# Callisto_LSOx10_v1p2.net
KiCad netlist of a schematic drawn in EAGLE
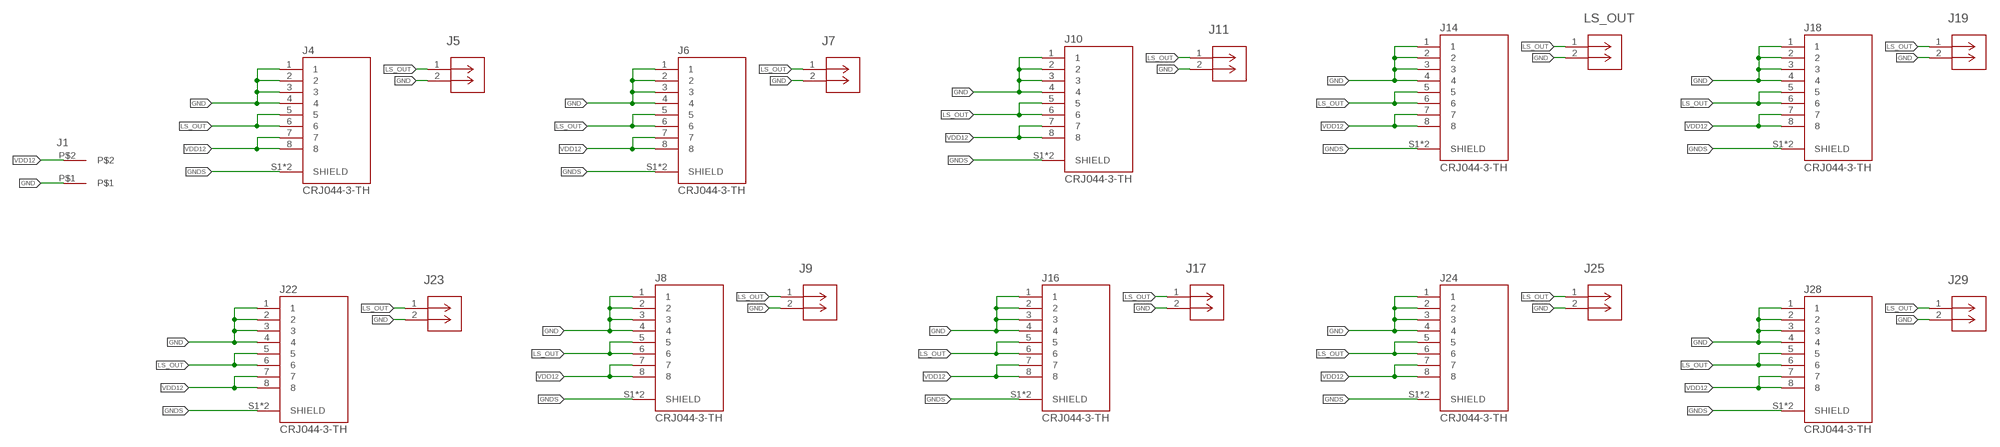
[diagram p0: schematic, sheet 1]

(export (version "E")
  (design (tool "Eeschema 10.0.6"))
  (components
    (comp (ref "J1")
      (value "2-pos")
      (footprint "eagle-import:2_3.81MM_PITCH")
      (fields (field (name "PARTNO") "691322310002"))
      (libsource (lib "eagle-import") (part "3.81MM_1_X_2_RT_ANGLE_PLUG_HEADER"))
    )
    (comp (ref "J4")
      (value "CRJ044-3-TH")
      (footprint "eagle-import:CUI_CRJ044-3-TH")
      (libsource (lib "eagle-import") (part "CRJ044-3-TH"))
    )
    (comp (ref "J5")
      (value "CONN_530470210_PICOBLADE_X_2")
      (footprint "eagle-import:CON_530470210_MOL")
      (fields
        (field (name "MANUFACTURER_PART_NUMBER") "530470210")
        (field (name "COPYRIGHT") "Copyright (C) 2022 Ultra Librarian. All rights reserved.")
      )
      (libsource (lib "eagle-import") (part "CONN_530470210_PICOBLADE_X_2"))
    )
    (comp (ref "J6")
      (value "CRJ044-3-TH")
      (footprint "eagle-import:CUI_CRJ044-3-TH")
      (libsource (lib "eagle-import") (part "CRJ044-3-TH"))
    )
    (comp (ref "J7")
      (value "CONN_530470210_PICOBLADE_X_2")
      (footprint "eagle-import:CON_530470210_MOL")
      (fields
        (field (name "MANUFACTURER_PART_NUMBER") "530470210")
        (field (name "COPYRIGHT") "Copyright (C) 2022 Ultra Librarian. All rights reserved.")
      )
      (libsource (lib "eagle-import") (part "CONN_530470210_PICOBLADE_X_2"))
    )
    (comp (ref "J8")
      (value "CRJ044-3-TH")
      (footprint "eagle-import:CUI_CRJ044-3-TH")
      (libsource (lib "eagle-import") (part "CRJ044-3-TH"))
    )
    (comp (ref "J9")
      (value "CONN_530470210_PICOBLADE_X_2")
      (footprint "eagle-import:CON_530470210_MOL")
      (fields
        (field (name "MANUFACTURER_PART_NUMBER") "530470210")
        (field (name "COPYRIGHT") "Copyright (C) 2022 Ultra Librarian. All rights reserved.")
      )
      (libsource (lib "eagle-import") (part "CONN_530470210_PICOBLADE_X_2"))
    )
    (comp (ref "J10")
      (value "CRJ044-3-TH")
      (footprint "eagle-import:CUI_CRJ044-3-TH")
      (libsource (lib "eagle-import") (part "CRJ044-3-TH"))
    )
    (comp (ref "J11")
      (value "CONN_530470210_PICOBLADE_X_2")
      (footprint "eagle-import:CON_530470210_MOL")
      (fields
        (field (name "MANUFACTURER_PART_NUMBER") "530470210")
        (field (name "COPYRIGHT") "Copyright (C) 2022 Ultra Librarian. All rights reserved.")
      )
      (libsource (lib "eagle-import") (part "CONN_530470210_PICOBLADE_X_2"))
    )
    (comp (ref "J14")
      (value "CRJ044-3-TH")
      (footprint "eagle-import:CUI_CRJ044-3-TH")
      (libsource (lib "eagle-import") (part "CRJ044-3-TH"))
    )
    (comp (ref "J16")
      (value "CRJ044-3-TH")
      (footprint "eagle-import:CUI_CRJ044-3-TH")
      (libsource (lib "eagle-import") (part "CRJ044-3-TH"))
    )
    (comp (ref "J17")
      (value "CONN_530470210_PICOBLADE_X_2")
      (footprint "eagle-import:CON_530470210_MOL")
      (fields
        (field (name "MANUFACTURER_PART_NUMBER") "530470210")
        (field (name "COPYRIGHT") "Copyright (C) 2022 Ultra Librarian. All rights reserved.")
      )
      (libsource (lib "eagle-import") (part "CONN_530470210_PICOBLADE_X_2"))
    )
    (comp (ref "J18")
      (value "CRJ044-3-TH")
      (footprint "eagle-import:CUI_CRJ044-3-TH")
      (libsource (lib "eagle-import") (part "CRJ044-3-TH"))
    )
    (comp (ref "J19")
      (value "CONN_530470210_PICOBLADE_X_2")
      (footprint "eagle-import:CON_530470210_MOL")
      (fields
        (field (name "MANUFACTURER_PART_NUMBER") "530470210")
        (field (name "COPYRIGHT") "Copyright (C) 2022 Ultra Librarian. All rights reserved.")
      )
      (libsource (lib "eagle-import") (part "CONN_530470210_PICOBLADE_X_2"))
    )
    (comp (ref "J22")
      (value "CRJ044-3-TH")
      (footprint "eagle-import:CUI_CRJ044-3-TH")
      (libsource (lib "eagle-import") (part "CRJ044-3-TH"))
    )
    (comp (ref "J23")
      (value "CONN_530470210_PICOBLADE_X_2")
      (footprint "eagle-import:CON_530470210_MOL")
      (fields
        (field (name "MANUFACTURER_PART_NUMBER") "530470210")
        (field (name "COPYRIGHT") "Copyright (C) 2022 Ultra Librarian. All rights reserved.")
      )
      (libsource (lib "eagle-import") (part "CONN_530470210_PICOBLADE_X_2"))
    )
    (comp (ref "J24")
      (value "CRJ044-3-TH")
      (footprint "eagle-import:CUI_CRJ044-3-TH")
      (libsource (lib "eagle-import") (part "CRJ044-3-TH"))
    )
    (comp (ref "J25")
      (value "CONN_530470210_PICOBLADE_X_2")
      (footprint "eagle-import:CON_530470210_MOL")
      (fields
        (field (name "MANUFACTURER_PART_NUMBER") "530470210")
        (field (name "COPYRIGHT") "Copyright (C) 2022 Ultra Librarian. All rights reserved.")
      )
      (libsource (lib "eagle-import") (part "CONN_530470210_PICOBLADE_X_2"))
    )
    (comp (ref "J28")
      (value "CRJ044-3-TH")
      (footprint "eagle-import:CUI_CRJ044-3-TH")
      (libsource (lib "eagle-import") (part "CRJ044-3-TH"))
    )
    (comp (ref "J29")
      (value "CONN_530470210_PICOBLADE_X_2")
      (footprint "eagle-import:CON_530470210_MOL")
      (fields
        (field (name "MANUFACTURER_PART_NUMBER") "530470210")
        (field (name "COPYRIGHT") "Copyright (C) 2022 Ultra Librarian. All rights reserved.")
      )
      (libsource (lib "eagle-import") (part "CONN_530470210_PICOBLADE_X_2"))
    )
    (comp (ref "LS_OUT")
      (value "CONN_530470210_PICOBLADE_X_2")
      (footprint "eagle-import:CON_530470210_MOL")
      (fields
        (field (name "MANUFACTURER_PART_NUMBER") "530470210")
        (field (name "COPYRIGHT") "Copyright (C) 2022 Ultra Librarian. All rights reserved.")
      )
      (libsource (lib "eagle-import") (part "CONN_530470210_PICOBLADE_X_2"))
    )
  )
  (nets
    (net (code "1") (name "GND") (class "Default")
      (node (ref "J1") (pin "P$1") (pinfunction "P$1_P$1") (pintype "bidirectional"))
      (node (ref "J10") (pin "1") (pinfunction "1_1") (pintype "passive"))
      (node (ref "J10") (pin "2") (pinfunction "2_2") (pintype "passive"))
      (node (ref "J10") (pin "3") (pinfunction "3_3") (pintype "passive"))
      (node (ref "J10") (pin "4") (pinfunction "4_4") (pintype "passive"))
      (node (ref "J11") (pin "2") (pinfunction "2_2") (pintype "passive"))
      (node (ref "J14") (pin "1") (pinfunction "1_1") (pintype "passive"))
      (node (ref "J14") (pin "2") (pinfunction "2_2") (pintype "passive"))
      (node (ref "J14") (pin "3") (pinfunction "3_3") (pintype "passive"))
      (node (ref "J14") (pin "4") (pinfunction "4_4") (pintype "passive"))
      (node (ref "J16") (pin "1") (pinfunction "1_1") (pintype "passive"))
      (node (ref "J16") (pin "2") (pinfunction "2_2") (pintype "passive"))
      (node (ref "J16") (pin "3") (pinfunction "3_3") (pintype "passive"))
      (node (ref "J16") (pin "4") (pinfunction "4_4") (pintype "passive"))
      (node (ref "J17") (pin "2") (pinfunction "2_2") (pintype "passive"))
      (node (ref "J18") (pin "1") (pinfunction "1_1") (pintype "passive"))
      (node (ref "J18") (pin "2") (pinfunction "2_2") (pintype "passive"))
      (node (ref "J18") (pin "3") (pinfunction "3_3") (pintype "passive"))
      (node (ref "J18") (pin "4") (pinfunction "4_4") (pintype "passive"))
      (node (ref "J19") (pin "2") (pinfunction "2_2") (pintype "passive"))
      (node (ref "J22") (pin "1") (pinfunction "1_1") (pintype "passive"))
      (node (ref "J22") (pin "2") (pinfunction "2_2") (pintype "passive"))
      (node (ref "J22") (pin "3") (pinfunction "3_3") (pintype "passive"))
      (node (ref "J22") (pin "4") (pinfunction "4_4") (pintype "passive"))
      (node (ref "J23") (pin "2") (pinfunction "2_2") (pintype "passive"))
      (node (ref "J24") (pin "1") (pinfunction "1_1") (pintype "passive"))
      (node (ref "J24") (pin "2") (pinfunction "2_2") (pintype "passive"))
      (node (ref "J24") (pin "3") (pinfunction "3_3") (pintype "passive"))
      (node (ref "J24") (pin "4") (pinfunction "4_4") (pintype "passive"))
      (node (ref "J25") (pin "2") (pinfunction "2_2") (pintype "passive"))
      (node (ref "J28") (pin "1") (pinfunction "1_1") (pintype "passive"))
      (node (ref "J28") (pin "2") (pinfunction "2_2") (pintype "passive"))
      (node (ref "J28") (pin "3") (pinfunction "3_3") (pintype "passive"))
      (node (ref "J28") (pin "4") (pinfunction "4_4") (pintype "passive"))
      (node (ref "J29") (pin "2") (pinfunction "2_2") (pintype "passive"))
      (node (ref "J4") (pin "1") (pinfunction "1_1") (pintype "passive"))
      (node (ref "J4") (pin "2") (pinfunction "2_2") (pintype "passive"))
      (node (ref "J4") (pin "3") (pinfunction "3_3") (pintype "passive"))
      (node (ref "J4") (pin "4") (pinfunction "4_4") (pintype "passive"))
      (node (ref "J5") (pin "2") (pinfunction "2_2") (pintype "passive"))
      (node (ref "J6") (pin "1") (pinfunction "1_1") (pintype "passive"))
      (node (ref "J6") (pin "2") (pinfunction "2_2") (pintype "passive"))
      (node (ref "J6") (pin "3") (pinfunction "3_3") (pintype "passive"))
      (node (ref "J6") (pin "4") (pinfunction "4_4") (pintype "passive"))
      (node (ref "J7") (pin "2") (pinfunction "2_2") (pintype "passive"))
      (node (ref "J8") (pin "1") (pinfunction "1_1") (pintype "passive"))
      (node (ref "J8") (pin "2") (pinfunction "2_2") (pintype "passive"))
      (node (ref "J8") (pin "3") (pinfunction "3_3") (pintype "passive"))
      (node (ref "J8") (pin "4") (pinfunction "4_4") (pintype "passive"))
      (node (ref "J9") (pin "2") (pinfunction "2_2") (pintype "passive"))
      (node (ref "LS_OUT") (pin "2") (pinfunction "2_2") (pintype "passive"))
    )
    (net (code "2") (name "GNDS") (class "Default")
      (node (ref "J10") (pin "S1") (pinfunction "SHIELD_S1") (pintype "passive"))
      (node (ref "J10") (pin "S2") (pinfunction "SHIELD_S2") (pintype "passive"))
      (node (ref "J14") (pin "S1") (pinfunction "SHIELD_S1") (pintype "passive"))
      (node (ref "J14") (pin "S2") (pinfunction "SHIELD_S2") (pintype "passive"))
      (node (ref "J16") (pin "S1") (pinfunction "SHIELD_S1") (pintype "passive"))
      (node (ref "J16") (pin "S2") (pinfunction "SHIELD_S2") (pintype "passive"))
      (node (ref "J18") (pin "S1") (pinfunction "SHIELD_S1") (pintype "passive"))
      (node (ref "J18") (pin "S2") (pinfunction "SHIELD_S2") (pintype "passive"))
      (node (ref "J22") (pin "S1") (pinfunction "SHIELD_S1") (pintype "passive"))
      (node (ref "J22") (pin "S2") (pinfunction "SHIELD_S2") (pintype "passive"))
      (node (ref "J24") (pin "S1") (pinfunction "SHIELD_S1") (pintype "passive"))
      (node (ref "J24") (pin "S2") (pinfunction "SHIELD_S2") (pintype "passive"))
      (node (ref "J28") (pin "S1") (pinfunction "SHIELD_S1") (pintype "passive"))
      (node (ref "J28") (pin "S2") (pinfunction "SHIELD_S2") (pintype "passive"))
      (node (ref "J4") (pin "S1") (pinfunction "SHIELD_S1") (pintype "passive"))
      (node (ref "J4") (pin "S2") (pinfunction "SHIELD_S2") (pintype "passive"))
      (node (ref "J6") (pin "S1") (pinfunction "SHIELD_S1") (pintype "passive"))
      (node (ref "J6") (pin "S2") (pinfunction "SHIELD_S2") (pintype "passive"))
      (node (ref "J8") (pin "S1") (pinfunction "SHIELD_S1") (pintype "passive"))
      (node (ref "J8") (pin "S2") (pinfunction "SHIELD_S2") (pintype "passive"))
    )
    (net (code "3") (name "LS_OUT") (class "Default")
      (node (ref "J10") (pin "5") (pinfunction "5_5") (pintype "passive"))
      (node (ref "J10") (pin "6") (pinfunction "6_6") (pintype "passive"))
      (node (ref "J11") (pin "1") (pinfunction "1_1") (pintype "passive"))
      (node (ref "J14") (pin "5") (pinfunction "5_5") (pintype "passive"))
      (node (ref "J14") (pin "6") (pinfunction "6_6") (pintype "passive"))
      (node (ref "J16") (pin "5") (pinfunction "5_5") (pintype "passive"))
      (node (ref "J16") (pin "6") (pinfunction "6_6") (pintype "passive"))
      (node (ref "J17") (pin "1") (pinfunction "1_1") (pintype "passive"))
      (node (ref "J18") (pin "5") (pinfunction "5_5") (pintype "passive"))
      (node (ref "J18") (pin "6") (pinfunction "6_6") (pintype "passive"))
      (node (ref "J19") (pin "1") (pinfunction "1_1") (pintype "passive"))
      (node (ref "J22") (pin "5") (pinfunction "5_5") (pintype "passive"))
      (node (ref "J22") (pin "6") (pinfunction "6_6") (pintype "passive"))
      (node (ref "J23") (pin "1") (pinfunction "1_1") (pintype "passive"))
      (node (ref "J24") (pin "5") (pinfunction "5_5") (pintype "passive"))
      (node (ref "J24") (pin "6") (pinfunction "6_6") (pintype "passive"))
      (node (ref "J25") (pin "1") (pinfunction "1_1") (pintype "passive"))
      (node (ref "J28") (pin "5") (pinfunction "5_5") (pintype "passive"))
      (node (ref "J28") (pin "6") (pinfunction "6_6") (pintype "passive"))
      (node (ref "J29") (pin "1") (pinfunction "1_1") (pintype "passive"))
      (node (ref "J4") (pin "5") (pinfunction "5_5") (pintype "passive"))
      (node (ref "J4") (pin "6") (pinfunction "6_6") (pintype "passive"))
      (node (ref "J5") (pin "1") (pinfunction "1_1") (pintype "passive"))
      (node (ref "J6") (pin "5") (pinfunction "5_5") (pintype "passive"))
      (node (ref "J6") (pin "6") (pinfunction "6_6") (pintype "passive"))
      (node (ref "J7") (pin "1") (pinfunction "1_1") (pintype "passive"))
      (node (ref "J8") (pin "5") (pinfunction "5_5") (pintype "passive"))
      (node (ref "J8") (pin "6") (pinfunction "6_6") (pintype "passive"))
      (node (ref "J9") (pin "1") (pinfunction "1_1") (pintype "passive"))
      (node (ref "LS_OUT") (pin "1") (pinfunction "1_1") (pintype "passive"))
    )
    (net (code "4") (name "VDD12") (class "Default")
      (node (ref "J1") (pin "P$2") (pinfunction "P$2_P$2") (pintype "bidirectional"))
      (node (ref "J10") (pin "7") (pinfunction "7_7") (pintype "passive"))
      (node (ref "J10") (pin "8") (pinfunction "8_8") (pintype "passive"))
      (node (ref "J14") (pin "7") (pinfunction "7_7") (pintype "passive"))
      (node (ref "J14") (pin "8") (pinfunction "8_8") (pintype "passive"))
      (node (ref "J16") (pin "7") (pinfunction "7_7") (pintype "passive"))
      (node (ref "J16") (pin "8") (pinfunction "8_8") (pintype "passive"))
      (node (ref "J18") (pin "7") (pinfunction "7_7") (pintype "passive"))
      (node (ref "J18") (pin "8") (pinfunction "8_8") (pintype "passive"))
      (node (ref "J22") (pin "7") (pinfunction "7_7") (pintype "passive"))
      (node (ref "J22") (pin "8") (pinfunction "8_8") (pintype "passive"))
      (node (ref "J24") (pin "7") (pinfunction "7_7") (pintype "passive"))
      (node (ref "J24") (pin "8") (pinfunction "8_8") (pintype "passive"))
      (node (ref "J28") (pin "7") (pinfunction "7_7") (pintype "passive"))
      (node (ref "J28") (pin "8") (pinfunction "8_8") (pintype "passive"))
      (node (ref "J4") (pin "7") (pinfunction "7_7") (pintype "passive"))
      (node (ref "J4") (pin "8") (pinfunction "8_8") (pintype "passive"))
      (node (ref "J6") (pin "7") (pinfunction "7_7") (pintype "passive"))
      (node (ref "J6") (pin "8") (pinfunction "8_8") (pintype "passive"))
      (node (ref "J8") (pin "7") (pinfunction "7_7") (pintype "passive"))
      (node (ref "J8") (pin "8") (pinfunction "8_8") (pintype "passive"))
    )
  )
)
